# Accumulator_HotDog.net
KiCad netlist of a schematic drawn in Altium Designer
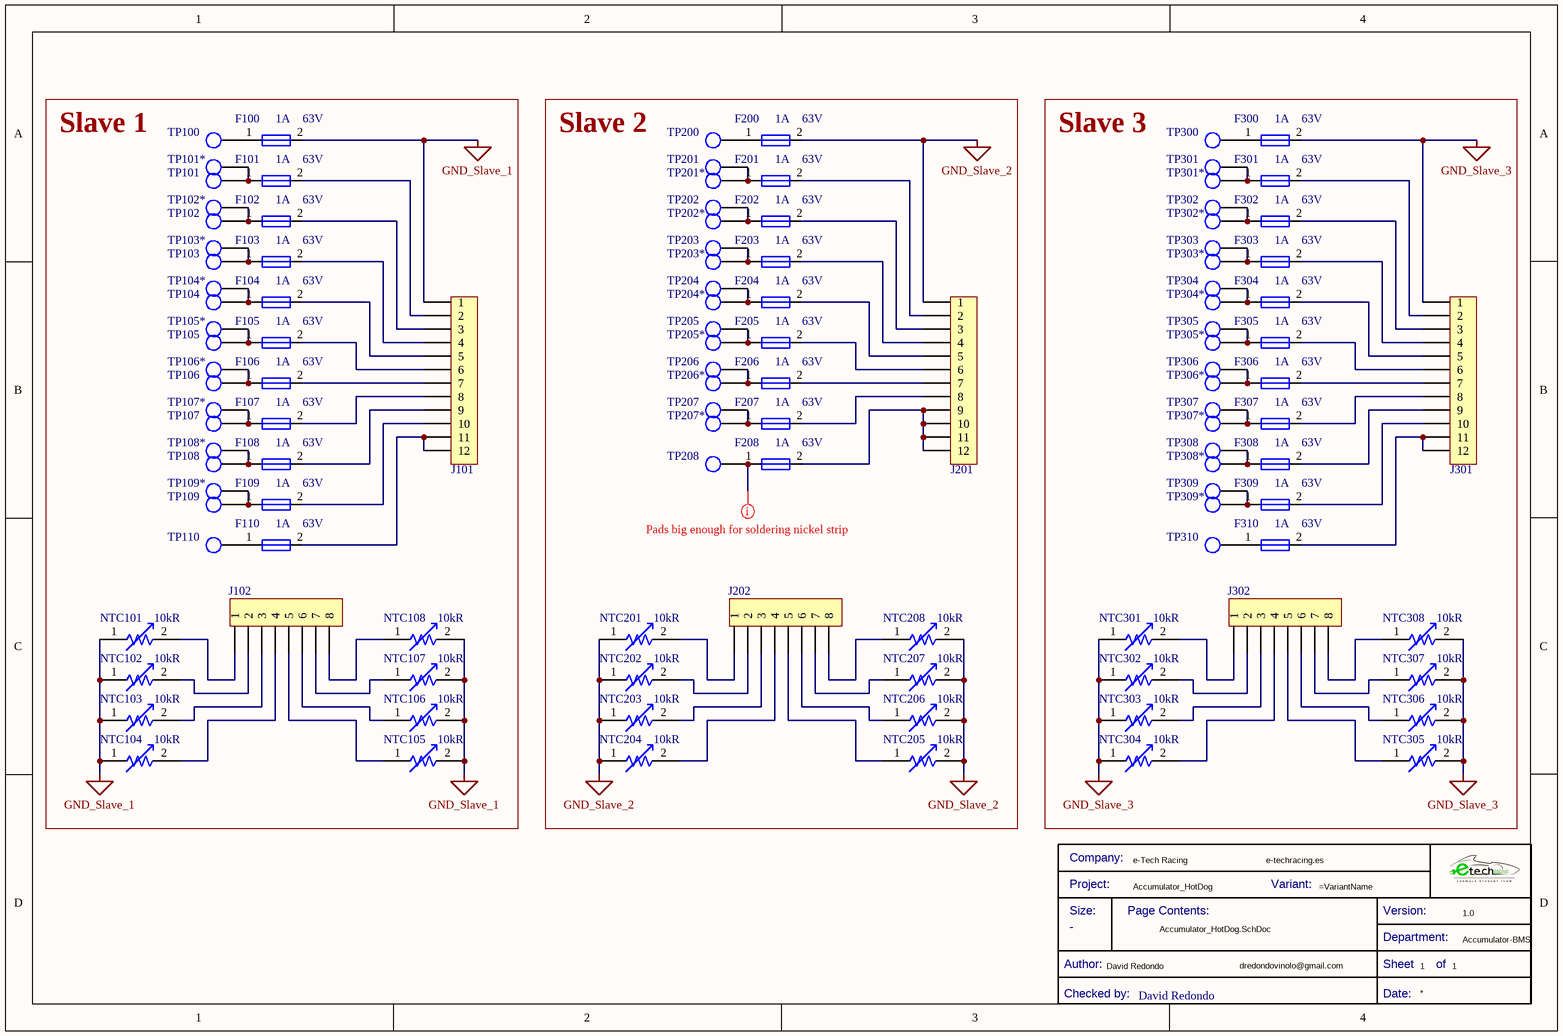
[diagram p0: Accumulator_HotDog.SchDoc]

(export (version "E")
  (design (tool "Eeschema 10.0.6"))
  (components
    (comp (ref "*")
      (value "Title Block_template")
      (description "Standard Title Block")
      (fields (field (name "SIZE") "-"))
      (libsource (lib "e-Tech_Racing") (part "Title Block_template"))
    )
    (comp (ref "F100")
      (value "0437001.WRA")
      (footprint "Fuse_1206")
      (description "Fuse Chip Fast Acting 1A 63V SMD Solder Pad 1206 Ceramic T/R Automotive")
      (fields
        (field (name "MANUFACTURER") "Littelfuse")
        (field (name "CURRENT RATING") "1A")
        (field (name "VOLTAGE RATING (DC)") "63V")
      )
      (libsource (lib "Filter components") (part "Fuse_1A_63V_1206"))
    )
    (comp (ref "F101")
      (value "0437001.WRA")
      (footprint "Fuse_1206")
      (description "Fuse Chip Fast Acting 1A 63V SMD Solder Pad 1206 Ceramic T/R Automotive")
      (fields
        (field (name "MANUFACTURER") "Littelfuse")
        (field (name "CURRENT RATING") "1A")
        (field (name "VOLTAGE RATING (DC)") "63V")
      )
      (libsource (lib "Filter components") (part "Fuse_1A_63V_1206"))
    )
    (comp (ref "F102")
      (value "0437001.WRA")
      (footprint "Fuse_1206")
      (description "Fuse Chip Fast Acting 1A 63V SMD Solder Pad 1206 Ceramic T/R Automotive")
      (fields
        (field (name "MANUFACTURER") "Littelfuse")
        (field (name "CURRENT RATING") "1A")
        (field (name "VOLTAGE RATING (DC)") "63V")
      )
      (libsource (lib "Filter components") (part "Fuse_1A_63V_1206"))
    )
    (comp (ref "F103")
      (value "0437001.WRA")
      (footprint "Fuse_1206")
      (description "Fuse Chip Fast Acting 1A 63V SMD Solder Pad 1206 Ceramic T/R Automotive")
      (fields
        (field (name "MANUFACTURER") "Littelfuse")
        (field (name "CURRENT RATING") "1A")
        (field (name "VOLTAGE RATING (DC)") "63V")
      )
      (libsource (lib "Filter components") (part "Fuse_1A_63V_1206"))
    )
    (comp (ref "F104")
      (value "0437001.WRA")
      (footprint "Fuse_1206")
      (description "Fuse Chip Fast Acting 1A 63V SMD Solder Pad 1206 Ceramic T/R Automotive")
      (fields
        (field (name "MANUFACTURER") "Littelfuse")
        (field (name "CURRENT RATING") "1A")
        (field (name "VOLTAGE RATING (DC)") "63V")
      )
      (libsource (lib "Filter components") (part "Fuse_1A_63V_1206"))
    )
    (comp (ref "F105")
      (value "0437001.WRA")
      (footprint "Fuse_1206")
      (description "Fuse Chip Fast Acting 1A 63V SMD Solder Pad 1206 Ceramic T/R Automotive")
      (fields
        (field (name "MANUFACTURER") "Littelfuse")
        (field (name "CURRENT RATING") "1A")
        (field (name "VOLTAGE RATING (DC)") "63V")
      )
      (libsource (lib "Filter components") (part "Fuse_1A_63V_1206"))
    )
    (comp (ref "F106")
      (value "0437001.WRA")
      (footprint "Fuse_1206")
      (description "Fuse Chip Fast Acting 1A 63V SMD Solder Pad 1206 Ceramic T/R Automotive")
      (fields
        (field (name "MANUFACTURER") "Littelfuse")
        (field (name "CURRENT RATING") "1A")
        (field (name "VOLTAGE RATING (DC)") "63V")
      )
      (libsource (lib "Filter components") (part "Fuse_1A_63V_1206"))
    )
    (comp (ref "F107")
      (value "0437001.WRA")
      (footprint "Fuse_1206")
      (description "Fuse Chip Fast Acting 1A 63V SMD Solder Pad 1206 Ceramic T/R Automotive")
      (fields
        (field (name "MANUFACTURER") "Littelfuse")
        (field (name "CURRENT RATING") "1A")
        (field (name "VOLTAGE RATING (DC)") "63V")
      )
      (libsource (lib "Filter components") (part "Fuse_1A_63V_1206"))
    )
    (comp (ref "F108")
      (value "0437001.WRA")
      (footprint "Fuse_1206")
      (description "Fuse Chip Fast Acting 1A 63V SMD Solder Pad 1206 Ceramic T/R Automotive")
      (fields
        (field (name "MANUFACTURER") "Littelfuse")
        (field (name "CURRENT RATING") "1A")
        (field (name "VOLTAGE RATING (DC)") "63V")
      )
      (libsource (lib "Filter components") (part "Fuse_1A_63V_1206"))
    )
    (comp (ref "F109")
      (value "0437001.WRA")
      (footprint "Fuse_1206")
      (description "Fuse Chip Fast Acting 1A 63V SMD Solder Pad 1206 Ceramic T/R Automotive")
      (fields
        (field (name "MANUFACTURER") "Littelfuse")
        (field (name "CURRENT RATING") "1A")
        (field (name "VOLTAGE RATING (DC)") "63V")
      )
      (libsource (lib "Filter components") (part "Fuse_1A_63V_1206"))
    )
    (comp (ref "F110")
      (value "0437001.WRA")
      (footprint "Fuse_1206")
      (description "Fuse Chip Fast Acting 1A 63V SMD Solder Pad 1206 Ceramic T/R Automotive")
      (fields
        (field (name "MANUFACTURER") "Littelfuse")
        (field (name "CURRENT RATING") "1A")
        (field (name "VOLTAGE RATING (DC)") "63V")
      )
      (libsource (lib "Filter components") (part "Fuse_1A_63V_1206"))
    )
    (comp (ref "F200")
      (value "0437001.WRA")
      (footprint "Fuse_1206")
      (description "Fuse Chip Fast Acting 1A 63V SMD Solder Pad 1206 Ceramic T/R Automotive")
      (fields
        (field (name "MANUFACTURER") "Littelfuse")
        (field (name "CURRENT RATING") "1A")
        (field (name "VOLTAGE RATING (DC)") "63V")
      )
      (libsource (lib "Filter components") (part "Fuse_1A_63V_1206"))
    )
    (comp (ref "F201")
      (value "0437001.WRA")
      (footprint "Fuse_1206")
      (description "Fuse Chip Fast Acting 1A 63V SMD Solder Pad 1206 Ceramic T/R Automotive")
      (fields
        (field (name "MANUFACTURER") "Littelfuse")
        (field (name "CURRENT RATING") "1A")
        (field (name "VOLTAGE RATING (DC)") "63V")
      )
      (libsource (lib "Filter components") (part "Fuse_1A_63V_1206"))
    )
    (comp (ref "F202")
      (value "0437001.WRA")
      (footprint "Fuse_1206")
      (description "Fuse Chip Fast Acting 1A 63V SMD Solder Pad 1206 Ceramic T/R Automotive")
      (fields
        (field (name "MANUFACTURER") "Littelfuse")
        (field (name "CURRENT RATING") "1A")
        (field (name "VOLTAGE RATING (DC)") "63V")
      )
      (libsource (lib "Filter components") (part "Fuse_1A_63V_1206"))
    )
    (comp (ref "F203")
      (value "0437001.WRA")
      (footprint "Fuse_1206")
      (description "Fuse Chip Fast Acting 1A 63V SMD Solder Pad 1206 Ceramic T/R Automotive")
      (fields
        (field (name "MANUFACTURER") "Littelfuse")
        (field (name "CURRENT RATING") "1A")
        (field (name "VOLTAGE RATING (DC)") "63V")
      )
      (libsource (lib "Filter components") (part "Fuse_1A_63V_1206"))
    )
    (comp (ref "F204")
      (value "0437001.WRA")
      (footprint "Fuse_1206")
      (description "Fuse Chip Fast Acting 1A 63V SMD Solder Pad 1206 Ceramic T/R Automotive")
      (fields
        (field (name "MANUFACTURER") "Littelfuse")
        (field (name "CURRENT RATING") "1A")
        (field (name "VOLTAGE RATING (DC)") "63V")
      )
      (libsource (lib "Filter components") (part "Fuse_1A_63V_1206"))
    )
    (comp (ref "F205")
      (value "0437001.WRA")
      (footprint "Fuse_1206")
      (description "Fuse Chip Fast Acting 1A 63V SMD Solder Pad 1206 Ceramic T/R Automotive")
      (fields
        (field (name "MANUFACTURER") "Littelfuse")
        (field (name "CURRENT RATING") "1A")
        (field (name "VOLTAGE RATING (DC)") "63V")
      )
      (libsource (lib "Filter components") (part "Fuse_1A_63V_1206"))
    )
    (comp (ref "F206")
      (value "0437001.WRA")
      (footprint "Fuse_1206")
      (description "Fuse Chip Fast Acting 1A 63V SMD Solder Pad 1206 Ceramic T/R Automotive")
      (fields
        (field (name "MANUFACTURER") "Littelfuse")
        (field (name "CURRENT RATING") "1A")
        (field (name "VOLTAGE RATING (DC)") "63V")
      )
      (libsource (lib "Filter components") (part "Fuse_1A_63V_1206"))
    )
    (comp (ref "F207")
      (value "0437001.WRA")
      (footprint "Fuse_1206")
      (description "Fuse Chip Fast Acting 1A 63V SMD Solder Pad 1206 Ceramic T/R Automotive")
      (fields
        (field (name "MANUFACTURER") "Littelfuse")
        (field (name "CURRENT RATING") "1A")
        (field (name "VOLTAGE RATING (DC)") "63V")
      )
      (libsource (lib "Filter components") (part "Fuse_1A_63V_1206"))
    )
    (comp (ref "F208")
      (value "0437001.WRA")
      (footprint "Fuse_1206")
      (description "Fuse Chip Fast Acting 1A 63V SMD Solder Pad 1206 Ceramic T/R Automotive")
      (fields
        (field (name "MANUFACTURER") "Littelfuse")
        (field (name "CURRENT RATING") "1A")
        (field (name "VOLTAGE RATING (DC)") "63V")
      )
      (libsource (lib "Filter components") (part "Fuse_1A_63V_1206"))
    )
    (comp (ref "F300")
      (value "0437001.WRA")
      (footprint "Fuse_1206")
      (description "Fuse Chip Fast Acting 1A 63V SMD Solder Pad 1206 Ceramic T/R Automotive")
      (fields
        (field (name "MANUFACTURER") "Littelfuse")
        (field (name "CURRENT RATING") "1A")
        (field (name "VOLTAGE RATING (DC)") "63V")
      )
      (libsource (lib "Filter components") (part "Fuse_1A_63V_1206"))
    )
    (comp (ref "F301")
      (value "0437001.WRA")
      (footprint "Fuse_1206")
      (description "Fuse Chip Fast Acting 1A 63V SMD Solder Pad 1206 Ceramic T/R Automotive")
      (fields
        (field (name "MANUFACTURER") "Littelfuse")
        (field (name "CURRENT RATING") "1A")
        (field (name "VOLTAGE RATING (DC)") "63V")
      )
      (libsource (lib "Filter components") (part "Fuse_1A_63V_1206"))
    )
    (comp (ref "F302")
      (value "0437001.WRA")
      (footprint "Fuse_1206")
      (description "Fuse Chip Fast Acting 1A 63V SMD Solder Pad 1206 Ceramic T/R Automotive")
      (fields
        (field (name "MANUFACTURER") "Littelfuse")
        (field (name "CURRENT RATING") "1A")
        (field (name "VOLTAGE RATING (DC)") "63V")
      )
      (libsource (lib "Filter components") (part "Fuse_1A_63V_1206"))
    )
    (comp (ref "F303")
      (value "0437001.WRA")
      (footprint "Fuse_1206")
      (description "Fuse Chip Fast Acting 1A 63V SMD Solder Pad 1206 Ceramic T/R Automotive")
      (fields
        (field (name "MANUFACTURER") "Littelfuse")
        (field (name "CURRENT RATING") "1A")
        (field (name "VOLTAGE RATING (DC)") "63V")
      )
      (libsource (lib "Filter components") (part "Fuse_1A_63V_1206"))
    )
    (comp (ref "F304")
      (value "0437001.WRA")
      (footprint "Fuse_1206")
      (description "Fuse Chip Fast Acting 1A 63V SMD Solder Pad 1206 Ceramic T/R Automotive")
      (fields
        (field (name "MANUFACTURER") "Littelfuse")
        (field (name "CURRENT RATING") "1A")
        (field (name "VOLTAGE RATING (DC)") "63V")
      )
      (libsource (lib "Filter components") (part "Fuse_1A_63V_1206"))
    )
    (comp (ref "F305")
      (value "0437001.WRA")
      (footprint "Fuse_1206")
      (description "Fuse Chip Fast Acting 1A 63V SMD Solder Pad 1206 Ceramic T/R Automotive")
      (fields
        (field (name "MANUFACTURER") "Littelfuse")
        (field (name "CURRENT RATING") "1A")
        (field (name "VOLTAGE RATING (DC)") "63V")
      )
      (libsource (lib "Filter components") (part "Fuse_1A_63V_1206"))
    )
    (comp (ref "F306")
      (value "0437001.WRA")
      (footprint "Fuse_1206")
      (description "Fuse Chip Fast Acting 1A 63V SMD Solder Pad 1206 Ceramic T/R Automotive")
      (fields
        (field (name "MANUFACTURER") "Littelfuse")
        (field (name "CURRENT RATING") "1A")
        (field (name "VOLTAGE RATING (DC)") "63V")
      )
      (libsource (lib "Filter components") (part "Fuse_1A_63V_1206"))
    )
    (comp (ref "F307")
      (value "0437001.WRA")
      (footprint "Fuse_1206")
      (description "Fuse Chip Fast Acting 1A 63V SMD Solder Pad 1206 Ceramic T/R Automotive")
      (fields
        (field (name "MANUFACTURER") "Littelfuse")
        (field (name "CURRENT RATING") "1A")
        (field (name "VOLTAGE RATING (DC)") "63V")
      )
      (libsource (lib "Filter components") (part "Fuse_1A_63V_1206"))
    )
    (comp (ref "F308")
      (value "0437001.WRA")
      (footprint "Fuse_1206")
      (description "Fuse Chip Fast Acting 1A 63V SMD Solder Pad 1206 Ceramic T/R Automotive")
      (fields
        (field (name "MANUFACTURER") "Littelfuse")
        (field (name "CURRENT RATING") "1A")
        (field (name "VOLTAGE RATING (DC)") "63V")
      )
      (libsource (lib "Filter components") (part "Fuse_1A_63V_1206"))
    )
    (comp (ref "F309")
      (value "0437001.WRA")
      (footprint "Fuse_1206")
      (description "Fuse Chip Fast Acting 1A 63V SMD Solder Pad 1206 Ceramic T/R Automotive")
      (fields
        (field (name "MANUFACTURER") "Littelfuse")
        (field (name "CURRENT RATING") "1A")
        (field (name "VOLTAGE RATING (DC)") "63V")
      )
      (libsource (lib "Filter components") (part "Fuse_1A_63V_1206"))
    )
    (comp (ref "F310")
      (value "0437001.WRA")
      (footprint "Fuse_1206")
      (description "Fuse Chip Fast Acting 1A 63V SMD Solder Pad 1206 Ceramic T/R Automotive")
      (fields
        (field (name "MANUFACTURER") "Littelfuse")
        (field (name "CURRENT RATING") "1A")
        (field (name "VOLTAGE RATING (DC)") "63V")
      )
      (libsource (lib "Filter components") (part "Fuse_1A_63V_1206"))
    )
    (comp (ref "J101")
      (value "J_MicroFit_1x12_V")
      (footprint "J_MicroFit_1x12_V")
      (description "Conn Power HDR 12 POS 3mm Solder ST Thru-Hole 12 Terminal 1 Port Micro-Fit 3.0™ Tray")
      (libsource (lib "Electromechanical") (part "J_MicroFit_1x12_V"))
    )
    (comp (ref "J102")
      (value "J_MicroFit_1x8_V")
      (footprint "J_MicroFit_1x8_V")
      (description "Conn Wire to Board HDR 8 POS 3mm Solder ST Top Entry Thru-Hole Micro-Fit 3.0™ Tray")
      (fields (field (name ".CREATOR") "DR"))
      (libsource (lib "Electromechanical") (part "J_MicroFit_1x8_V"))
    )
    (comp (ref "J201")
      (value "J_MicroFit_1x12_V")
      (footprint "J_MicroFit_1x12_V")
      (description "Conn Power HDR 12 POS 3mm Solder ST Thru-Hole 12 Terminal 1 Port Micro-Fit 3.0™ Tray")
      (libsource (lib "Electromechanical") (part "J_MicroFit_1x12_V"))
    )
    (comp (ref "J202")
      (value "J_MicroFit_1x8_V")
      (footprint "J_MicroFit_1x8_V")
      (description "Conn Wire to Board HDR 8 POS 3mm Solder ST Top Entry Thru-Hole Micro-Fit 3.0™ Tray")
      (fields (field (name ".CREATOR") "DR"))
      (libsource (lib "Electromechanical") (part "J_MicroFit_1x8_V"))
    )
    (comp (ref "J301")
      (value "J_MicroFit_1x12_V")
      (footprint "J_MicroFit_1x12_V")
      (description "Conn Power HDR 12 POS 3mm Solder ST Thru-Hole 12 Terminal 1 Port Micro-Fit 3.0™ Tray")
      (libsource (lib "Electromechanical") (part "J_MicroFit_1x12_V"))
    )
    (comp (ref "J302")
      (value "J_MicroFit_1x8_V")
      (footprint "J_MicroFit_1x8_V")
      (description "Conn Wire to Board HDR 8 POS 3mm Solder ST Top Entry Thru-Hole Micro-Fit 3.0™ Tray")
      (fields (field (name ".CREATOR") "DR"))
      (libsource (lib "Electromechanical") (part "J_MicroFit_1x8_V"))
    )
    (comp (ref "NTC101")
      (value "NXRT15XV103FA1B040")
      (footprint "NTC_NXRT15XV103FA1B040")
      (description "NXR Series 10 kOhm 3900 K ±1% Bead NTC Thermistor Sensor")
      (fields (field (name "TOLERANCE") "1%") (field (name "RESISTANCE") "10kR"))
      (libsource (lib "Sensors") (part "NTC_NXRT15XV103FA1B040"))
    )
    (comp (ref "NTC102")
      (value "NXRT15XV103FA1B040")
      (footprint "NTC_NXRT15XV103FA1B040")
      (description "NXR Series 10 kOhm 3900 K ±1% Bead NTC Thermistor Sensor")
      (fields (field (name "TOLERANCE") "1%") (field (name "RESISTANCE") "10kR"))
      (libsource (lib "Sensors") (part "NTC_NXRT15XV103FA1B040"))
    )
    (comp (ref "NTC103")
      (value "NXRT15XV103FA1B040")
      (footprint "NTC_NXRT15XV103FA1B040")
      (description "NXR Series 10 kOhm 3900 K ±1% Bead NTC Thermistor Sensor")
      (fields (field (name "TOLERANCE") "1%") (field (name "RESISTANCE") "10kR"))
      (libsource (lib "Sensors") (part "NTC_NXRT15XV103FA1B040"))
    )
    (comp (ref "NTC104")
      (value "NXRT15XV103FA1B040")
      (footprint "NTC_NXRT15XV103FA1B040")
      (description "NXR Series 10 kOhm 3900 K ±1% Bead NTC Thermistor Sensor")
      (fields (field (name "TOLERANCE") "1%") (field (name "RESISTANCE") "10kR"))
      (libsource (lib "Sensors") (part "NTC_NXRT15XV103FA1B040"))
    )
    (comp (ref "NTC105")
      (value "NXRT15XV103FA1B040")
      (footprint "NTC_NXRT15XV103FA1B040")
      (description "NXR Series 10 kOhm 3900 K ±1% Bead NTC Thermistor Sensor")
      (fields (field (name "TOLERANCE") "1%") (field (name "RESISTANCE") "10kR"))
      (libsource (lib "Sensors") (part "NTC_NXRT15XV103FA1B040"))
    )
    (comp (ref "NTC106")
      (value "NXRT15XV103FA1B040")
      (footprint "NTC_NXRT15XV103FA1B040")
      (description "NXR Series 10 kOhm 3900 K ±1% Bead NTC Thermistor Sensor")
      (fields (field (name "TOLERANCE") "1%") (field (name "RESISTANCE") "10kR"))
      (libsource (lib "Sensors") (part "NTC_NXRT15XV103FA1B040"))
    )
    (comp (ref "NTC107")
      (value "NXRT15XV103FA1B040")
      (footprint "NTC_NXRT15XV103FA1B040")
      (description "NXR Series 10 kOhm 3900 K ±1% Bead NTC Thermistor Sensor")
      (fields (field (name "TOLERANCE") "1%") (field (name "RESISTANCE") "10kR"))
      (libsource (lib "Sensors") (part "NTC_NXRT15XV103FA1B040"))
    )
    (comp (ref "NTC108")
      (value "NXRT15XV103FA1B040")
      (footprint "NTC_NXRT15XV103FA1B040")
      (description "NXR Series 10 kOhm 3900 K ±1% Bead NTC Thermistor Sensor")
      (fields (field (name "TOLERANCE") "1%") (field (name "RESISTANCE") "10kR"))
      (libsource (lib "Sensors") (part "NTC_NXRT15XV103FA1B040"))
    )
    (comp (ref "NTC201")
      (value "NXRT15XV103FA1B040")
      (footprint "NTC_NXRT15XV103FA1B040")
      (description "NXR Series 10 kOhm 3900 K ±1% Bead NTC Thermistor Sensor")
      (fields (field (name "TOLERANCE") "1%") (field (name "RESISTANCE") "10kR"))
      (libsource (lib "Sensors") (part "NTC_NXRT15XV103FA1B040"))
    )
    (comp (ref "NTC202")
      (value "NXRT15XV103FA1B040")
      (footprint "NTC_NXRT15XV103FA1B040")
      (description "NXR Series 10 kOhm 3900 K ±1% Bead NTC Thermistor Sensor")
      (fields (field (name "TOLERANCE") "1%") (field (name "RESISTANCE") "10kR"))
      (libsource (lib "Sensors") (part "NTC_NXRT15XV103FA1B040"))
    )
    (comp (ref "NTC203")
      (value "NXRT15XV103FA1B040")
      (footprint "NTC_NXRT15XV103FA1B040")
      (description "NXR Series 10 kOhm 3900 K ±1% Bead NTC Thermistor Sensor")
      (fields (field (name "TOLERANCE") "1%") (field (name "RESISTANCE") "10kR"))
      (libsource (lib "Sensors") (part "NTC_NXRT15XV103FA1B040"))
    )
    (comp (ref "NTC204")
      (value "NXRT15XV103FA1B040")
      (footprint "NTC_NXRT15XV103FA1B040")
      (description "NXR Series 10 kOhm 3900 K ±1% Bead NTC Thermistor Sensor")
      (fields (field (name "TOLERANCE") "1%") (field (name "RESISTANCE") "10kR"))
      (libsource (lib "Sensors") (part "NTC_NXRT15XV103FA1B040"))
    )
    (comp (ref "NTC205")
      (value "NXRT15XV103FA1B040")
      (footprint "NTC_NXRT15XV103FA1B040")
      (description "NXR Series 10 kOhm 3900 K ±1% Bead NTC Thermistor Sensor")
      (fields (field (name "TOLERANCE") "1%") (field (name "RESISTANCE") "10kR"))
      (libsource (lib "Sensors") (part "NTC_NXRT15XV103FA1B040"))
    )
    (comp (ref "NTC206")
      (value "NXRT15XV103FA1B040")
      (footprint "NTC_NXRT15XV103FA1B040")
      (description "NXR Series 10 kOhm 3900 K ±1% Bead NTC Thermistor Sensor")
      (fields (field (name "TOLERANCE") "1%") (field (name "RESISTANCE") "10kR"))
      (libsource (lib "Sensors") (part "NTC_NXRT15XV103FA1B040"))
    )
    (comp (ref "NTC207")
      (value "NXRT15XV103FA1B040")
      (footprint "NTC_NXRT15XV103FA1B040")
      (description "NXR Series 10 kOhm 3900 K ±1% Bead NTC Thermistor Sensor")
      (fields (field (name "TOLERANCE") "1%") (field (name "RESISTANCE") "10kR"))
      (libsource (lib "Sensors") (part "NTC_NXRT15XV103FA1B040"))
    )
    (comp (ref "NTC208")
      (value "NXRT15XV103FA1B040")
      (footprint "NTC_NXRT15XV103FA1B040")
      (description "NXR Series 10 kOhm 3900 K ±1% Bead NTC Thermistor Sensor")
      (fields (field (name "TOLERANCE") "1%") (field (name "RESISTANCE") "10kR"))
      (libsource (lib "Sensors") (part "NTC_NXRT15XV103FA1B040"))
    )
    (comp (ref "NTC301")
      (value "NXRT15XV103FA1B040")
      (footprint "NTC_NXRT15XV103FA1B040")
      (description "NXR Series 10 kOhm 3900 K ±1% Bead NTC Thermistor Sensor")
      (fields (field (name "TOLERANCE") "1%") (field (name "RESISTANCE") "10kR"))
      (libsource (lib "Sensors") (part "NTC_NXRT15XV103FA1B040"))
    )
    (comp (ref "NTC302")
      (value "NXRT15XV103FA1B040")
      (footprint "NTC_NXRT15XV103FA1B040")
      (description "NXR Series 10 kOhm 3900 K ±1% Bead NTC Thermistor Sensor")
      (fields (field (name "TOLERANCE") "1%") (field (name "RESISTANCE") "10kR"))
      (libsource (lib "Sensors") (part "NTC_NXRT15XV103FA1B040"))
    )
    (comp (ref "NTC303")
      (value "NXRT15XV103FA1B040")
      (footprint "NTC_NXRT15XV103FA1B040")
      (description "NXR Series 10 kOhm 3900 K ±1% Bead NTC Thermistor Sensor")
      (fields (field (name "TOLERANCE") "1%") (field (name "RESISTANCE") "10kR"))
      (libsource (lib "Sensors") (part "NTC_NXRT15XV103FA1B040"))
    )
    (comp (ref "NTC304")
      (value "NXRT15XV103FA1B040")
      (footprint "NTC_NXRT15XV103FA1B040")
      (description "NXR Series 10 kOhm 3900 K ±1% Bead NTC Thermistor Sensor")
      (fields (field (name "TOLERANCE") "1%") (field (name "RESISTANCE") "10kR"))
      (libsource (lib "Sensors") (part "NTC_NXRT15XV103FA1B040"))
    )
    (comp (ref "NTC305")
      (value "NXRT15XV103FA1B040")
      (footprint "NTC_NXRT15XV103FA1B040")
      (description "NXR Series 10 kOhm 3900 K ±1% Bead NTC Thermistor Sensor")
      (fields (field (name "TOLERANCE") "1%") (field (name "RESISTANCE") "10kR"))
      (libsource (lib "Sensors") (part "NTC_NXRT15XV103FA1B040"))
    )
    (comp (ref "NTC306")
      (value "NXRT15XV103FA1B040")
      (footprint "NTC_NXRT15XV103FA1B040")
      (description "NXR Series 10 kOhm 3900 K ±1% Bead NTC Thermistor Sensor")
      (fields (field (name "TOLERANCE") "1%") (field (name "RESISTANCE") "10kR"))
      (libsource (lib "Sensors") (part "NTC_NXRT15XV103FA1B040"))
    )
    (comp (ref "NTC307")
      (value "NXRT15XV103FA1B040")
      (footprint "NTC_NXRT15XV103FA1B040")
      (description "NXR Series 10 kOhm 3900 K ±1% Bead NTC Thermistor Sensor")
      (fields (field (name "TOLERANCE") "1%") (field (name "RESISTANCE") "10kR"))
      (libsource (lib "Sensors") (part "NTC_NXRT15XV103FA1B040"))
    )
    (comp (ref "NTC308")
      (value "NXRT15XV103FA1B040")
      (footprint "NTC_NXRT15XV103FA1B040")
      (description "NXR Series 10 kOhm 3900 K ±1% Bead NTC Thermistor Sensor")
      (fields (field (name "TOLERANCE") "1%") (field (name "RESISTANCE") "10kR"))
      (libsource (lib "Sensors") (part "NTC_NXRT15XV103FA1B040"))
    )
    (comp (ref "TP100")
      (value "TestPoint")
      (footprint "TestPoint")
      (description "Test Point 1x1 mm")
      (libsource (lib "e-Tech_Racing") (part "TestPoint"))
    )
    (comp (ref "TP101")
      (value "TestPoint")
      (footprint "TestPoint")
      (description "Test Point 1x1 mm")
      (libsource (lib "e-Tech_Racing") (part "TestPoint"))
    )
    (comp (ref "TP101*")
      (value "TestPoint")
      (footprint "TestPoint")
      (description "Test Point 1x1 mm")
      (libsource (lib "e-Tech_Racing") (part "TestPoint"))
    )
    (comp (ref "TP102")
      (value "TestPoint")
      (footprint "TestPoint")
      (description "Test Point 1x1 mm")
      (libsource (lib "e-Tech_Racing") (part "TestPoint"))
    )
    (comp (ref "TP102*")
      (value "TestPoint")
      (footprint "TestPoint")
      (description "Test Point 1x1 mm")
      (libsource (lib "e-Tech_Racing") (part "TestPoint"))
    )
    (comp (ref "TP103")
      (value "TestPoint")
      (footprint "TestPoint")
      (description "Test Point 1x1 mm")
      (libsource (lib "e-Tech_Racing") (part "TestPoint"))
    )
    (comp (ref "TP103*")
      (value "TestPoint")
      (footprint "TestPoint")
      (description "Test Point 1x1 mm")
      (libsource (lib "e-Tech_Racing") (part "TestPoint"))
    )
    (comp (ref "TP104")
      (value "TestPoint")
      (footprint "TestPoint")
      (description "Test Point 1x1 mm")
      (libsource (lib "e-Tech_Racing") (part "TestPoint"))
    )
    (comp (ref "TP104*")
      (value "TestPoint")
      (footprint "TestPoint")
      (description "Test Point 1x1 mm")
      (libsource (lib "e-Tech_Racing") (part "TestPoint"))
    )
    (comp (ref "TP105")
      (value "TestPoint")
      (footprint "TestPoint")
      (description "Test Point 1x1 mm")
      (libsource (lib "e-Tech_Racing") (part "TestPoint"))
    )
    (comp (ref "TP105*")
      (value "TestPoint")
      (footprint "TestPoint")
      (description "Test Point 1x1 mm")
      (libsource (lib "e-Tech_Racing") (part "TestPoint"))
    )
    (comp (ref "TP106")
      (value "TestPoint")
      (footprint "TestPoint")
      (description "Test Point 1x1 mm")
      (libsource (lib "e-Tech_Racing") (part "TestPoint"))
    )
    (comp (ref "TP106*")
      (value "TestPoint")
      (footprint "TestPoint")
      (description "Test Point 1x1 mm")
      (libsource (lib "e-Tech_Racing") (part "TestPoint"))
    )
    (comp (ref "TP107")
      (value "TestPoint")
      (footprint "TestPoint")
      (description "Test Point 1x1 mm")
      (libsource (lib "e-Tech_Racing") (part "TestPoint"))
    )
    (comp (ref "TP107*")
      (value "TestPoint")
      (footprint "TestPoint")
      (description "Test Point 1x1 mm")
      (libsource (lib "e-Tech_Racing") (part "TestPoint"))
    )
    (comp (ref "TP108")
      (value "TestPoint")
      (footprint "TestPoint")
      (description "Test Point 1x1 mm")
      (libsource (lib "e-Tech_Racing") (part "TestPoint"))
    )
    (comp (ref "TP108*")
      (value "TestPoint")
      (footprint "TestPoint")
      (description "Test Point 1x1 mm")
      (libsource (lib "e-Tech_Racing") (part "TestPoint"))
    )
    (comp (ref "TP109")
      (value "TestPoint")
      (footprint "TestPoint")
      (description "Test Point 1x1 mm")
      (libsource (lib "e-Tech_Racing") (part "TestPoint"))
    )
    (comp (ref "TP109*")
      (value "TestPoint")
      (footprint "TestPoint")
      (description "Test Point 1x1 mm")
      (libsource (lib "e-Tech_Racing") (part "TestPoint"))
    )
    (comp (ref "TP110")
      (value "TestPoint")
      (footprint "TestPoint")
      (description "Test Point 1x1 mm")
      (libsource (lib "e-Tech_Racing") (part "TestPoint"))
    )
    (comp (ref "TP200")
      (value "TestPoint")
      (footprint "TestPoint")
      (description "Test Point 1x1 mm")
      (libsource (lib "e-Tech_Racing") (part "TestPoint"))
    )
    (comp (ref "TP201")
      (value "TestPoint")
      (footprint "TestPoint")
      (description "Test Point 1x1 mm")
      (libsource (lib "e-Tech_Racing") (part "TestPoint"))
    )
    (comp (ref "TP201*")
      (value "TestPoint")
      (footprint "TestPoint")
      (description "Test Point 1x1 mm")
      (libsource (lib "e-Tech_Racing") (part "TestPoint"))
    )
    (comp (ref "TP202")
      (value "TestPoint")
      (footprint "TestPoint")
      (description "Test Point 1x1 mm")
      (libsource (lib "e-Tech_Racing") (part "TestPoint"))
    )
    (comp (ref "TP202*")
      (value "TestPoint")
      (footprint "TestPoint")
      (description "Test Point 1x1 mm")
      (libsource (lib "e-Tech_Racing") (part "TestPoint"))
    )
    (comp (ref "TP203")
      (value "TestPoint")
      (footprint "TestPoint")
      (description "Test Point 1x1 mm")
      (libsource (lib "e-Tech_Racing") (part "TestPoint"))
    )
    (comp (ref "TP203*")
      (value "TestPoint")
      (footprint "TestPoint")
      (description "Test Point 1x1 mm")
      (libsource (lib "e-Tech_Racing") (part "TestPoint"))
    )
    (comp (ref "TP204")
      (value "TestPoint")
      (footprint "TestPoint")
      (description "Test Point 1x1 mm")
      (libsource (lib "e-Tech_Racing") (part "TestPoint"))
    )
    (comp (ref "TP204*")
      (value "TestPoint")
      (footprint "TestPoint")
      (description "Test Point 1x1 mm")
      (libsource (lib "e-Tech_Racing") (part "TestPoint"))
    )
    (comp (ref "TP205")
      (value "TestPoint")
      (footprint "TestPoint")
      (description "Test Point 1x1 mm")
      (libsource (lib "e-Tech_Racing") (part "TestPoint"))
    )
    (comp (ref "TP205*")
      (value "TestPoint")
      (footprint "TestPoint")
      (description "Test Point 1x1 mm")
      (libsource (lib "e-Tech_Racing") (part "TestPoint"))
    )
    (comp (ref "TP206")
      (value "TestPoint")
      (footprint "TestPoint")
      (description "Test Point 1x1 mm")
      (libsource (lib "e-Tech_Racing") (part "TestPoint"))
    )
    (comp (ref "TP206*")
      (value "TestPoint")
      (footprint "TestPoint")
      (description "Test Point 1x1 mm")
      (libsource (lib "e-Tech_Racing") (part "TestPoint"))
    )
    (comp (ref "TP207")
      (value "TestPoint")
      (footprint "TestPoint")
      (description "Test Point 1x1 mm")
      (libsource (lib "e-Tech_Racing") (part "TestPoint"))
    )
    (comp (ref "TP207*")
      (value "TestPoint")
      (footprint "TestPoint")
      (description "Test Point 1x1 mm")
      (libsource (lib "e-Tech_Racing") (part "TestPoint"))
    )
    (comp (ref "TP208")
      (value "TestPoint")
      (footprint "TestPoint")
      (description "Test Point 1x1 mm")
      (libsource (lib "e-Tech_Racing") (part "TestPoint"))
    )
    (comp (ref "TP300")
      (value "TestPoint")
      (footprint "TestPoint")
      (description "Test Point 1x1 mm")
      (libsource (lib "e-Tech_Racing") (part "TestPoint"))
    )
    (comp (ref "TP301")
      (value "TestPoint")
      (footprint "TestPoint")
      (description "Test Point 1x1 mm")
      (libsource (lib "e-Tech_Racing") (part "TestPoint"))
    )
    (comp (ref "TP301*")
      (value "TestPoint")
      (footprint "TestPoint")
      (description "Test Point 1x1 mm")
      (libsource (lib "e-Tech_Racing") (part "TestPoint"))
    )
    (comp (ref "TP302")
      (value "TestPoint")
      (footprint "TestPoint")
      (description "Test Point 1x1 mm")
      (libsource (lib "e-Tech_Racing") (part "TestPoint"))
    )
    (comp (ref "TP302*")
      (value "TestPoint")
      (footprint "TestPoint")
      (description "Test Point 1x1 mm")
      (libsource (lib "e-Tech_Racing") (part "TestPoint"))
    )
    (comp (ref "TP303")
      (value "TestPoint")
      (footprint "TestPoint")
      (description "Test Point 1x1 mm")
      (libsource (lib "e-Tech_Racing") (part "TestPoint"))
    )
    (comp (ref "TP303*")
      (value "TestPoint")
      (footprint "TestPoint")
      (description "Test Point 1x1 mm")
      (libsource (lib "e-Tech_Racing") (part "TestPoint"))
    )
    (comp (ref "TP304")
      (value "TestPoint")
      (footprint "TestPoint")
      (description "Test Point 1x1 mm")
      (libsource (lib "e-Tech_Racing") (part "TestPoint"))
    )
    (comp (ref "TP304*")
      (value "TestPoint")
      (footprint "TestPoint")
      (description "Test Point 1x1 mm")
      (libsource (lib "e-Tech_Racing") (part "TestPoint"))
    )
    (comp (ref "TP305")
      (value "TestPoint")
      (footprint "TestPoint")
      (description "Test Point 1x1 mm")
      (libsource (lib "e-Tech_Racing") (part "TestPoint"))
    )
    (comp (ref "TP305*")
      (value "TestPoint")
      (footprint "TestPoint")
      (description "Test Point 1x1 mm")
      (libsource (lib "e-Tech_Racing") (part "TestPoint"))
    )
    (comp (ref "TP306")
      (value "TestPoint")
      (footprint "TestPoint")
      (description "Test Point 1x1 mm")
      (libsource (lib "e-Tech_Racing") (part "TestPoint"))
    )
    (comp (ref "TP306*")
      (value "TestPoint")
      (footprint "TestPoint")
      (description "Test Point 1x1 mm")
      (libsource (lib "e-Tech_Racing") (part "TestPoint"))
    )
    (comp (ref "TP307")
      (value "TestPoint")
      (footprint "TestPoint")
      (description "Test Point 1x1 mm")
      (libsource (lib "e-Tech_Racing") (part "TestPoint"))
    )
    (comp (ref "TP307*")
      (value "TestPoint")
      (footprint "TestPoint")
      (description "Test Point 1x1 mm")
      (libsource (lib "e-Tech_Racing") (part "TestPoint"))
    )
    (comp (ref "TP308")
      (value "TestPoint")
      (footprint "TestPoint")
      (description "Test Point 1x1 mm")
      (libsource (lib "e-Tech_Racing") (part "TestPoint"))
    )
    (comp (ref "TP308*")
      (value "TestPoint")
      (footprint "TestPoint")
      (description "Test Point 1x1 mm")
      (libsource (lib "e-Tech_Racing") (part "TestPoint"))
    )
    (comp (ref "TP309")
      (value "TestPoint")
      (footprint "TestPoint")
      (description "Test Point 1x1 mm")
      (libsource (lib "e-Tech_Racing") (part "TestPoint"))
    )
    (comp (ref "TP309*")
      (value "TestPoint")
      (footprint "TestPoint")
      (description "Test Point 1x1 mm")
      (libsource (lib "e-Tech_Racing") (part "TestPoint"))
    )
    (comp (ref "TP310")
      (value "TestPoint")
      (footprint "TestPoint")
      (description "Test Point 1x1 mm")
      (libsource (lib "e-Tech_Racing") (part "TestPoint"))
    )
  )
  (nets
    (net (code "1") (name "GND_Slave_1") (class "Default")
      (node (ref "F100") (pin "2") (pinfunction "2_2") (pintype "passive"))
      (node (ref "J101") (pin "1") (pinfunction "1_1") (pintype "passive"))
      (node (ref "NTC101") (pin "1") (pinfunction "2_1") (pintype "passive"))
      (node (ref "NTC102") (pin "1") (pinfunction "2_1") (pintype "passive"))
      (node (ref "NTC103") (pin "1") (pinfunction "2_1") (pintype "passive"))
      (node (ref "NTC104") (pin "1") (pinfunction "2_1") (pintype "passive"))
      (node (ref "NTC105") (pin "2") (pinfunction "2_2") (pintype "passive"))
      (node (ref "NTC106") (pin "2") (pinfunction "2_2") (pintype "passive"))
      (node (ref "NTC107") (pin "2") (pinfunction "2_2") (pintype "passive"))
      (node (ref "NTC108") (pin "2") (pinfunction "2_2") (pintype "passive"))
    )
    (net (code "2") (name "GND_Slave_2") (class "Default")
      (node (ref "F200") (pin "2") (pinfunction "2_2") (pintype "passive"))
      (node (ref "J201") (pin "1") (pinfunction "1_1") (pintype "passive"))
      (node (ref "NTC201") (pin "1") (pinfunction "2_1") (pintype "passive"))
      (node (ref "NTC202") (pin "1") (pinfunction "2_1") (pintype "passive"))
      (node (ref "NTC203") (pin "1") (pinfunction "2_1") (pintype "passive"))
      (node (ref "NTC204") (pin "1") (pinfunction "2_1") (pintype "passive"))
      (node (ref "NTC205") (pin "2") (pinfunction "2_2") (pintype "passive"))
      (node (ref "NTC206") (pin "2") (pinfunction "2_2") (pintype "passive"))
      (node (ref "NTC207") (pin "2") (pinfunction "2_2") (pintype "passive"))
      (node (ref "NTC208") (pin "2") (pinfunction "2_2") (pintype "passive"))
    )
    (net (code "3") (name "GND_Slave_3") (class "Default")
      (node (ref "F300") (pin "2") (pinfunction "2_2") (pintype "passive"))
      (node (ref "J301") (pin "1") (pinfunction "1_1") (pintype "passive"))
      (node (ref "NTC301") (pin "1") (pinfunction "2_1") (pintype "passive"))
      (node (ref "NTC302") (pin "1") (pinfunction "2_1") (pintype "passive"))
      (node (ref "NTC303") (pin "1") (pinfunction "2_1") (pintype "passive"))
      (node (ref "NTC304") (pin "1") (pinfunction "2_1") (pintype "passive"))
      (node (ref "NTC305") (pin "2") (pinfunction "2_2") (pintype "passive"))
      (node (ref "NTC306") (pin "2") (pinfunction "2_2") (pintype "passive"))
      (node (ref "NTC307") (pin "2") (pinfunction "2_2") (pintype "passive"))
      (node (ref "NTC308") (pin "2") (pinfunction "2_2") (pintype "passive"))
    )
    (net (code "4") (name "Net-(F100-Pad1)") (class "Default")
      (node (ref "F100") (pin "1") (pinfunction "1_1") (pintype "passive"))
      (node (ref "TP100") (pin "1") (pinfunction "1_1") (pintype "passive"))
    )
    (net (code "5") (name "Net-(F101-Pad1)") (class "Default")
      (node (ref "F101") (pin "1") (pinfunction "1_1") (pintype "passive"))
      (node (ref "TP101") (pin "1") (pinfunction "1_1") (pintype "passive"))
      (node (ref "TP101*") (pin "1") (pinfunction "1_1") (pintype "passive"))
    )
    (net (code "6") (name "Net-(F101-Pad2)") (class "Default")
      (node (ref "F101") (pin "2") (pinfunction "2_2") (pintype "passive"))
      (node (ref "J101") (pin "2") (pinfunction "2_2") (pintype "passive"))
    )
    (net (code "7") (name "Net-(F102-Pad1)") (class "Default")
      (node (ref "F102") (pin "1") (pinfunction "1_1") (pintype "passive"))
      (node (ref "TP102") (pin "1") (pinfunction "1_1") (pintype "passive"))
      (node (ref "TP102*") (pin "1") (pinfunction "1_1") (pintype "passive"))
    )
    (net (code "8") (name "Net-(F102-Pad2)") (class "Default")
      (node (ref "F102") (pin "2") (pinfunction "2_2") (pintype "passive"))
      (node (ref "J101") (pin "3") (pinfunction "3_3") (pintype "passive"))
    )
    (net (code "9") (name "Net-(F103-Pad1)") (class "Default")
      (node (ref "F103") (pin "1") (pinfunction "1_1") (pintype "passive"))
      (node (ref "TP103") (pin "1") (pinfunction "1_1") (pintype "passive"))
      (node (ref "TP103*") (pin "1") (pinfunction "1_1") (pintype "passive"))
    )
    (net (code "10") (name "Net-(F103-Pad2)") (class "Default")
      (node (ref "F103") (pin "2") (pinfunction "2_2") (pintype "passive"))
      (node (ref "J101") (pin "4") (pinfunction "4_4") (pintype "passive"))
    )
    (net (code "11") (name "Net-(F104-Pad1)") (class "Default")
      (node (ref "F104") (pin "1") (pinfunction "1_1") (pintype "passive"))
      (node (ref "TP104") (pin "1") (pinfunction "1_1") (pintype "passive"))
      (node (ref "TP104*") (pin "1") (pinfunction "1_1") (pintype "passive"))
    )
    (net (code "12") (name "Net-(F104-Pad2)") (class "Default")
      (node (ref "F104") (pin "2") (pinfunction "2_2") (pintype "passive"))
      (node (ref "J101") (pin "5") (pinfunction "5_5") (pintype "passive"))
    )
    (net (code "13") (name "Net-(F105-Pad1)") (class "Default")
      (node (ref "F105") (pin "1") (pinfunction "1_1") (pintype "passive"))
      (node (ref "TP105") (pin "1") (pinfunction "1_1") (pintype "passive"))
      (node (ref "TP105*") (pin "1") (pinfunction "1_1") (pintype "passive"))
    )
    (net (code "14") (name "Net-(F105-Pad2)") (class "Default")
      (node (ref "F105") (pin "2") (pinfunction "2_2") (pintype "passive"))
      (node (ref "J101") (pin "6") (pinfunction "6_6") (pintype "passive"))
    )
    (net (code "15") (name "Net-(F106-Pad1)") (class "Default")
      (node (ref "F106") (pin "1") (pinfunction "1_1") (pintype "passive"))
      (node (ref "TP106") (pin "1") (pinfunction "1_1") (pintype "passive"))
      (node (ref "TP106*") (pin "1") (pinfunction "1_1") (pintype "passive"))
    )
    (net (code "16") (name "Net-(F106-Pad2)") (class "Default")
      (node (ref "F106") (pin "2") (pinfunction "2_2") (pintype "passive"))
      (node (ref "J101") (pin "7") (pinfunction "7_7") (pintype "passive"))
    )
    (net (code "17") (name "Net-(F107-Pad1)") (class "Default")
      (node (ref "F107") (pin "1") (pinfunction "1_1") (pintype "passive"))
      (node (ref "TP107") (pin "1") (pinfunction "1_1") (pintype "passive"))
      (node (ref "TP107*") (pin "1") (pinfunction "1_1") (pintype "passive"))
    )
    (net (code "18") (name "Net-(F107-Pad2)") (class "Default")
      (node (ref "F107") (pin "2") (pinfunction "2_2") (pintype "passive"))
      (node (ref "J101") (pin "8") (pinfunction "8_8") (pintype "passive"))
    )
    (net (code "19") (name "Net-(F108-Pad1)") (class "Default")
      (node (ref "F108") (pin "1") (pinfunction "1_1") (pintype "passive"))
      (node (ref "TP108") (pin "1") (pinfunction "1_1") (pintype "passive"))
      (node (ref "TP108*") (pin "1") (pinfunction "1_1") (pintype "passive"))
    )
    (net (code "20") (name "Net-(F108-Pad2)") (class "Default")
      (node (ref "F108") (pin "2") (pinfunction "2_2") (pintype "passive"))
      (node (ref "J101") (pin "9") (pinfunction "9_9") (pintype "passive"))
    )
    (net (code "21") (name "Net-(F109-Pad1)") (class "Default")
      (node (ref "F109") (pin "1") (pinfunction "1_1") (pintype "passive"))
      (node (ref "TP109") (pin "1") (pinfunction "1_1") (pintype "passive"))
      (node (ref "TP109*") (pin "1") (pinfunction "1_1") (pintype "passive"))
    )
    (net (code "22") (name "Net-(F109-Pad2)") (class "Default")
      (node (ref "F109") (pin "2") (pinfunction "2_2") (pintype "passive"))
      (node (ref "J101") (pin "10") (pinfunction "10_10") (pintype "passive"))
    )
    (net (code "23") (name "Net-(F110-Pad1)") (class "Default")
      (node (ref "F110") (pin "1") (pinfunction "1_1") (pintype "passive"))
      (node (ref "TP110") (pin "1") (pinfunction "1_1") (pintype "passive"))
    )
    (net (code "24") (name "Net-(F110-Pad2)") (class "Default")
      (node (ref "F110") (pin "2") (pinfunction "2_2") (pintype "passive"))
      (node (ref "J101") (pin "11") (pinfunction "11_11") (pintype "passive"))
      (node (ref "J101") (pin "12") (pinfunction "12_12") (pintype "passive"))
    )
    (net (code "25") (name "Net-(F200-Pad1)") (class "Default")
      (node (ref "F200") (pin "1") (pinfunction "1_1") (pintype "passive"))
      (node (ref "TP200") (pin "1") (pinfunction "1_1") (pintype "passive"))
    )
    (net (code "26") (name "Net-(F201-Pad1)") (class "Default")
      (node (ref "F201") (pin "1") (pinfunction "1_1") (pintype "passive"))
      (node (ref "TP201") (pin "1") (pinfunction "1_1") (pintype "passive"))
      (node (ref "TP201*") (pin "1") (pinfunction "1_1") (pintype "passive"))
    )
    (net (code "27") (name "Net-(F201-Pad2)") (class "Default")
      (node (ref "F201") (pin "2") (pinfunction "2_2") (pintype "passive"))
      (node (ref "J201") (pin "2") (pinfunction "2_2") (pintype "passive"))
    )
    (net (code "28") (name "Net-(F202-Pad1)") (class "Default")
      (node (ref "F202") (pin "1") (pinfunction "1_1") (pintype "passive"))
      (node (ref "TP202") (pin "1") (pinfunction "1_1") (pintype "passive"))
      (node (ref "TP202*") (pin "1") (pinfunction "1_1") (pintype "passive"))
    )
    (net (code "29") (name "Net-(F202-Pad2)") (class "Default")
      (node (ref "F202") (pin "2") (pinfunction "2_2") (pintype "passive"))
      (node (ref "J201") (pin "3") (pinfunction "3_3") (pintype "passive"))
    )
    (net (code "30") (name "Net-(F203-Pad1)") (class "Default")
      (node (ref "F203") (pin "1") (pinfunction "1_1") (pintype "passive"))
      (node (ref "TP203") (pin "1") (pinfunction "1_1") (pintype "passive"))
      (node (ref "TP203*") (pin "1") (pinfunction "1_1") (pintype "passive"))
    )
    (net (code "31") (name "Net-(F203-Pad2)") (class "Default")
      (node (ref "F203") (pin "2") (pinfunction "2_2") (pintype "passive"))
      (node (ref "J201") (pin "4") (pinfunction "4_4") (pintype "passive"))
    )
    (net (code "32") (name "Net-(F204-Pad1)") (class "Default")
      (node (ref "F204") (pin "1") (pinfunction "1_1") (pintype "passive"))
      (node (ref "TP204") (pin "1") (pinfunction "1_1") (pintype "passive"))
      (node (ref "TP204*") (pin "1") (pinfunction "1_1") (pintype "passive"))
    )
    (net (code "33") (name "Net-(F204-Pad2)") (class "Default")
      (node (ref "F204") (pin "2") (pinfunction "2_2") (pintype "passive"))
      (node (ref "J201") (pin "5") (pinfunction "5_5") (pintype "passive"))
    )
    (net (code "34") (name "Net-(F205-Pad1)") (class "Default")
      (node (ref "F205") (pin "1") (pinfunction "1_1") (pintype "passive"))
      (node (ref "TP205") (pin "1") (pinfunction "1_1") (pintype "passive"))
      (node (ref "TP205*") (pin "1") (pinfunction "1_1") (pintype "passive"))
    )
    (net (code "35") (name "Net-(F205-Pad2)") (class "Default")
      (node (ref "F205") (pin "2") (pinfunction "2_2") (pintype "passive"))
      (node (ref "J201") (pin "6") (pinfunction "6_6") (pintype "passive"))
    )
    (net (code "36") (name "Net-(F206-Pad1)") (class "Default")
      (node (ref "F206") (pin "1") (pinfunction "1_1") (pintype "passive"))
      (node (ref "TP206") (pin "1") (pinfunction "1_1") (pintype "passive"))
      (node (ref "TP206*") (pin "1") (pinfunction "1_1") (pintype "passive"))
    )
    (net (code "37") (name "Net-(F206-Pad2)") (class "Default")
      (node (ref "F206") (pin "2") (pinfunction "2_2") (pintype "passive"))
      (node (ref "J201") (pin "7") (pinfunction "7_7") (pintype "passive"))
    )
    (net (code "38") (name "Net-(F207-Pad1)") (class "Default")
      (node (ref "F207") (pin "1") (pinfunction "1_1") (pintype "passive"))
      (node (ref "TP207") (pin "1") (pinfunction "1_1") (pintype "passive"))
      (node (ref "TP207*") (pin "1") (pinfunction "1_1") (pintype "passive"))
    )
    (net (code "39") (name "Net-(F207-Pad2)") (class "Default")
      (node (ref "F207") (pin "2") (pinfunction "2_2") (pintype "passive"))
      (node (ref "J201") (pin "8") (pinfunction "8_8") (pintype "passive"))
    )
    (net (code "40") (name "Net-(F208-Pad1)") (class "Default")
      (node (ref "F208") (pin "1") (pinfunction "1_1") (pintype "passive"))
      (node (ref "TP208") (pin "1") (pinfunction "1_1") (pintype "passive"))
    )
    (net (code "41") (name "Net-(F208-Pad2)") (class "Default")
      (node (ref "F208") (pin "2") (pinfunction "2_2") (pintype "passive"))
      (node (ref "J201") (pin "10") (pinfunction "10_10") (pintype "passive"))
      (node (ref "J201") (pin "11") (pinfunction "11_11") (pintype "passive"))
      (node (ref "J201") (pin "12") (pinfunction "12_12") (pintype "passive"))
      (node (ref "J201") (pin "9") (pinfunction "9_9") (pintype "passive"))
    )
    (net (code "42") (name "Net-(F300-Pad1)") (class "Default")
      (node (ref "F300") (pin "1") (pinfunction "1_1") (pintype "passive"))
      (node (ref "TP300") (pin "1") (pinfunction "1_1") (pintype "passive"))
    )
    (net (code "43") (name "Net-(F301-Pad1)") (class "Default")
      (node (ref "F301") (pin "1") (pinfunction "1_1") (pintype "passive"))
      (node (ref "TP301") (pin "1") (pinfunction "1_1") (pintype "passive"))
      (node (ref "TP301*") (pin "1") (pinfunction "1_1") (pintype "passive"))
    )
    (net (code "44") (name "Net-(F301-Pad2)") (class "Default")
      (node (ref "F301") (pin "2") (pinfunction "2_2") (pintype "passive"))
      (node (ref "J301") (pin "2") (pinfunction "2_2") (pintype "passive"))
    )
    (net (code "45") (name "Net-(F302-Pad1)") (class "Default")
      (node (ref "F302") (pin "1") (pinfunction "1_1") (pintype "passive"))
      (node (ref "TP302") (pin "1") (pinfunction "1_1") (pintype "passive"))
      (node (ref "TP302*") (pin "1") (pinfunction "1_1") (pintype "passive"))
    )
    (net (code "46") (name "Net-(F302-Pad2)") (class "Default")
      (node (ref "F302") (pin "2") (pinfunction "2_2") (pintype "passive"))
      (node (ref "J301") (pin "3") (pinfunction "3_3") (pintype "passive"))
    )
    (net (code "47") (name "Net-(F303-Pad1)") (class "Default")
      (node (ref "F303") (pin "1") (pinfunction "1_1") (pintype "passive"))
      (node (ref "TP303") (pin "1") (pinfunction "1_1") (pintype "passive"))
      (node (ref "TP303*") (pin "1") (pinfunction "1_1") (pintype "passive"))
    )
    (net (code "48") (name "Net-(F303-Pad2)") (class "Default")
      (node (ref "F303") (pin "2") (pinfunction "2_2") (pintype "passive"))
      (node (ref "J301") (pin "4") (pinfunction "4_4") (pintype "passive"))
    )
    (net (code "49") (name "Net-(F304-Pad1)") (class "Default")
      (node (ref "F304") (pin "1") (pinfunction "1_1") (pintype "passive"))
      (node (ref "TP304") (pin "1") (pinfunction "1_1") (pintype "passive"))
      (node (ref "TP304*") (pin "1") (pinfunction "1_1") (pintype "passive"))
    )
    (net (code "50") (name "Net-(F304-Pad2)") (class "Default")
      (node (ref "F304") (pin "2") (pinfunction "2_2") (pintype "passive"))
      (node (ref "J301") (pin "5") (pinfunction "5_5") (pintype "passive"))
    )
    (net (code "51") (name "Net-(F305-Pad1)") (class "Default")
      (node (ref "F305") (pin "1") (pinfunction "1_1") (pintype "passive"))
      (node (ref "TP305") (pin "1") (pinfunction "1_1") (pintype "passive"))
      (node (ref "TP305*") (pin "1") (pinfunction "1_1") (pintype "passive"))
    )
    (net (code "52") (name "Net-(F305-Pad2)") (class "Default")
      (node (ref "F305") (pin "2") (pinfunction "2_2") (pintype "passive"))
      (node (ref "J301") (pin "6") (pinfunction "6_6") (pintype "passive"))
    )
    (net (code "53") (name "Net-(F306-Pad1)") (class "Default")
      (node (ref "F306") (pin "1") (pinfunction "1_1") (pintype "passive"))
      (node (ref "TP306") (pin "1") (pinfunction "1_1") (pintype "passive"))
      (node (ref "TP306*") (pin "1") (pinfunction "1_1") (pintype "passive"))
    )
    (net (code "54") (name "Net-(F306-Pad2)") (class "Default")
      (node (ref "F306") (pin "2") (pinfunction "2_2") (pintype "passive"))
      (node (ref "J301") (pin "7") (pinfunction "7_7") (pintype "passive"))
    )
    (net (code "55") (name "Net-(F307-Pad1)") (class "Default")
      (node (ref "F307") (pin "1") (pinfunction "1_1") (pintype "passive"))
      (node (ref "TP307") (pin "1") (pinfunction "1_1") (pintype "passive"))
      (node (ref "TP307*") (pin "1") (pinfunction "1_1") (pintype "passive"))
    )
    (net (code "56") (name "Net-(F307-Pad2)") (class "Default")
      (node (ref "F307") (pin "2") (pinfunction "2_2") (pintype "passive"))
      (node (ref "J301") (pin "8") (pinfunction "8_8") (pintype "passive"))
    )
    (net (code "57") (name "Net-(F308-Pad1)") (class "Default")
      (node (ref "F308") (pin "1") (pinfunction "1_1") (pintype "passive"))
      (node (ref "TP308") (pin "1") (pinfunction "1_1") (pintype "passive"))
      (node (ref "TP308*") (pin "1") (pinfunction "1_1") (pintype "passive"))
    )
    (net (code "58") (name "Net-(F308-Pad2)") (class "Default")
      (node (ref "F308") (pin "2") (pinfunction "2_2") (pintype "passive"))
      (node (ref "J301") (pin "9") (pinfunction "9_9") (pintype "passive"))
    )
    (net (code "59") (name "Net-(F309-Pad1)") (class "Default")
      (node (ref "F309") (pin "1") (pinfunction "1_1") (pintype "passive"))
      (node (ref "TP309") (pin "1") (pinfunction "1_1") (pintype "passive"))
      (node (ref "TP309*") (pin "1") (pinfunction "1_1") (pintype "passive"))
    )
    (net (code "60") (name "Net-(F309-Pad2)") (class "Default")
      (node (ref "F309") (pin "2") (pinfunction "2_2") (pintype "passive"))
      (node (ref "J301") (pin "10") (pinfunction "10_10") (pintype "passive"))
    )
    (net (code "61") (name "Net-(F310-Pad1)") (class "Default")
      (node (ref "F310") (pin "1") (pinfunction "1_1") (pintype "passive"))
      (node (ref "TP310") (pin "1") (pinfunction "1_1") (pintype "passive"))
    )
    (net (code "62") (name "Net-(F310-Pad2)") (class "Default")
      (node (ref "F310") (pin "2") (pinfunction "2_2") (pintype "passive"))
      (node (ref "J301") (pin "11") (pinfunction "11_11") (pintype "passive"))
      (node (ref "J301") (pin "12") (pinfunction "12_12") (pintype "passive"))
    )
    (net (code "63") (name "Net-(J102-Pad1)") (class "Default")
      (node (ref "J102") (pin "1") (pinfunction "1_1") (pintype "passive"))
      (node (ref "NTC101") (pin "2") (pinfunction "2_2") (pintype "passive"))
    )
    (net (code "64") (name "Net-(J102-Pad2)") (class "Default")
      (node (ref "J102") (pin "2") (pinfunction "2_2") (pintype "passive"))
      (node (ref "NTC102") (pin "2") (pinfunction "2_2") (pintype "passive"))
    )
    (net (code "65") (name "Net-(J102-Pad3)") (class "Default")
      (node (ref "J102") (pin "3") (pinfunction "3_3") (pintype "passive"))
      (node (ref "NTC103") (pin "2") (pinfunction "2_2") (pintype "passive"))
    )
    (net (code "66") (name "Net-(J102-Pad4)") (class "Default")
      (node (ref "J102") (pin "4") (pinfunction "4_4") (pintype "passive"))
      (node (ref "NTC104") (pin "2") (pinfunction "2_2") (pintype "passive"))
    )
    (net (code "67") (name "Net-(J102-Pad5)") (class "Default")
      (node (ref "J102") (pin "5") (pinfunction "5_5") (pintype "passive"))
      (node (ref "NTC105") (pin "1") (pinfunction "2_1") (pintype "passive"))
    )
    (net (code "68") (name "Net-(J102-Pad6)") (class "Default")
      (node (ref "J102") (pin "6") (pinfunction "6_6") (pintype "passive"))
      (node (ref "NTC106") (pin "1") (pinfunction "2_1") (pintype "passive"))
    )
    (net (code "69") (name "Net-(J102-Pad7)") (class "Default")
      (node (ref "J102") (pin "7") (pinfunction "7_7") (pintype "passive"))
      (node (ref "NTC107") (pin "1") (pinfunction "2_1") (pintype "passive"))
    )
    (net (code "70") (name "Net-(J102-Pad8)") (class "Default")
      (node (ref "J102") (pin "8") (pinfunction "8_8") (pintype "passive"))
      (node (ref "NTC108") (pin "1") (pinfunction "2_1") (pintype "passive"))
    )
    (net (code "71") (name "Net-(J202-Pad1)") (class "Default")
      (node (ref "J202") (pin "1") (pinfunction "1_1") (pintype "passive"))
      (node (ref "NTC201") (pin "2") (pinfunction "2_2") (pintype "passive"))
    )
    (net (code "72") (name "Net-(J202-Pad2)") (class "Default")
      (node (ref "J202") (pin "2") (pinfunction "2_2") (pintype "passive"))
      (node (ref "NTC202") (pin "2") (pinfunction "2_2") (pintype "passive"))
    )
    (net (code "73") (name "Net-(J202-Pad3)") (class "Default")
      (node (ref "J202") (pin "3") (pinfunction "3_3") (pintype "passive"))
      (node (ref "NTC203") (pin "2") (pinfunction "2_2") (pintype "passive"))
    )
    (net (code "74") (name "Net-(J202-Pad4)") (class "Default")
      (node (ref "J202") (pin "4") (pinfunction "4_4") (pintype "passive"))
      (node (ref "NTC204") (pin "2") (pinfunction "2_2") (pintype "passive"))
    )
    (net (code "75") (name "Net-(J202-Pad5)") (class "Default")
      (node (ref "J202") (pin "5") (pinfunction "5_5") (pintype "passive"))
      (node (ref "NTC205") (pin "1") (pinfunction "2_1") (pintype "passive"))
    )
    (net (code "76") (name "Net-(J202-Pad6)") (class "Default")
      (node (ref "J202") (pin "6") (pinfunction "6_6") (pintype "passive"))
      (node (ref "NTC206") (pin "1") (pinfunction "2_1") (pintype "passive"))
    )
    (net (code "77") (name "Net-(J202-Pad7)") (class "Default")
      (node (ref "J202") (pin "7") (pinfunction "7_7") (pintype "passive"))
      (node (ref "NTC207") (pin "1") (pinfunction "2_1") (pintype "passive"))
    )
    (net (code "78") (name "Net-(J202-Pad8)") (class "Default")
      (node (ref "J202") (pin "8") (pinfunction "8_8") (pintype "passive"))
      (node (ref "NTC208") (pin "1") (pinfunction "2_1") (pintype "passive"))
    )
    (net (code "79") (name "Net-(J302-Pad1)") (class "Default")
      (node (ref "J302") (pin "1") (pinfunction "1_1") (pintype "passive"))
      (node (ref "NTC301") (pin "2") (pinfunction "2_2") (pintype "passive"))
    )
    (net (code "80") (name "Net-(J302-Pad2)") (class "Default")
      (node (ref "J302") (pin "2") (pinfunction "2_2") (pintype "passive"))
      (node (ref "NTC302") (pin "2") (pinfunction "2_2") (pintype "passive"))
    )
    (net (code "81") (name "Net-(J302-Pad3)") (class "Default")
      (node (ref "J302") (pin "3") (pinfunction "3_3") (pintype "passive"))
      (node (ref "NTC303") (pin "2") (pinfunction "2_2") (pintype "passive"))
    )
    (net (code "82") (name "Net-(J302-Pad4)") (class "Default")
      (node (ref "J302") (pin "4") (pinfunction "4_4") (pintype "passive"))
      (node (ref "NTC304") (pin "2") (pinfunction "2_2") (pintype "passive"))
    )
    (net (code "83") (name "Net-(J302-Pad5)") (class "Default")
      (node (ref "J302") (pin "5") (pinfunction "5_5") (pintype "passive"))
      (node (ref "NTC305") (pin "1") (pinfunction "2_1") (pintype "passive"))
    )
    (net (code "84") (name "Net-(J302-Pad6)") (class "Default")
      (node (ref "J302") (pin "6") (pinfunction "6_6") (pintype "passive"))
      (node (ref "NTC306") (pin "1") (pinfunction "2_1") (pintype "passive"))
    )
    (net (code "85") (name "Net-(J302-Pad7)") (class "Default")
      (node (ref "J302") (pin "7") (pinfunction "7_7") (pintype "passive"))
      (node (ref "NTC307") (pin "1") (pinfunction "2_1") (pintype "passive"))
    )
    (net (code "86") (name "Net-(J302-Pad8)") (class "Default")
      (node (ref "J302") (pin "8") (pinfunction "8_8") (pintype "passive"))
      (node (ref "NTC308") (pin "1") (pinfunction "2_1") (pintype "passive"))
    )
  )
)
